# 01.net
KiCad netlist of a schematic drawn in Altium Designer
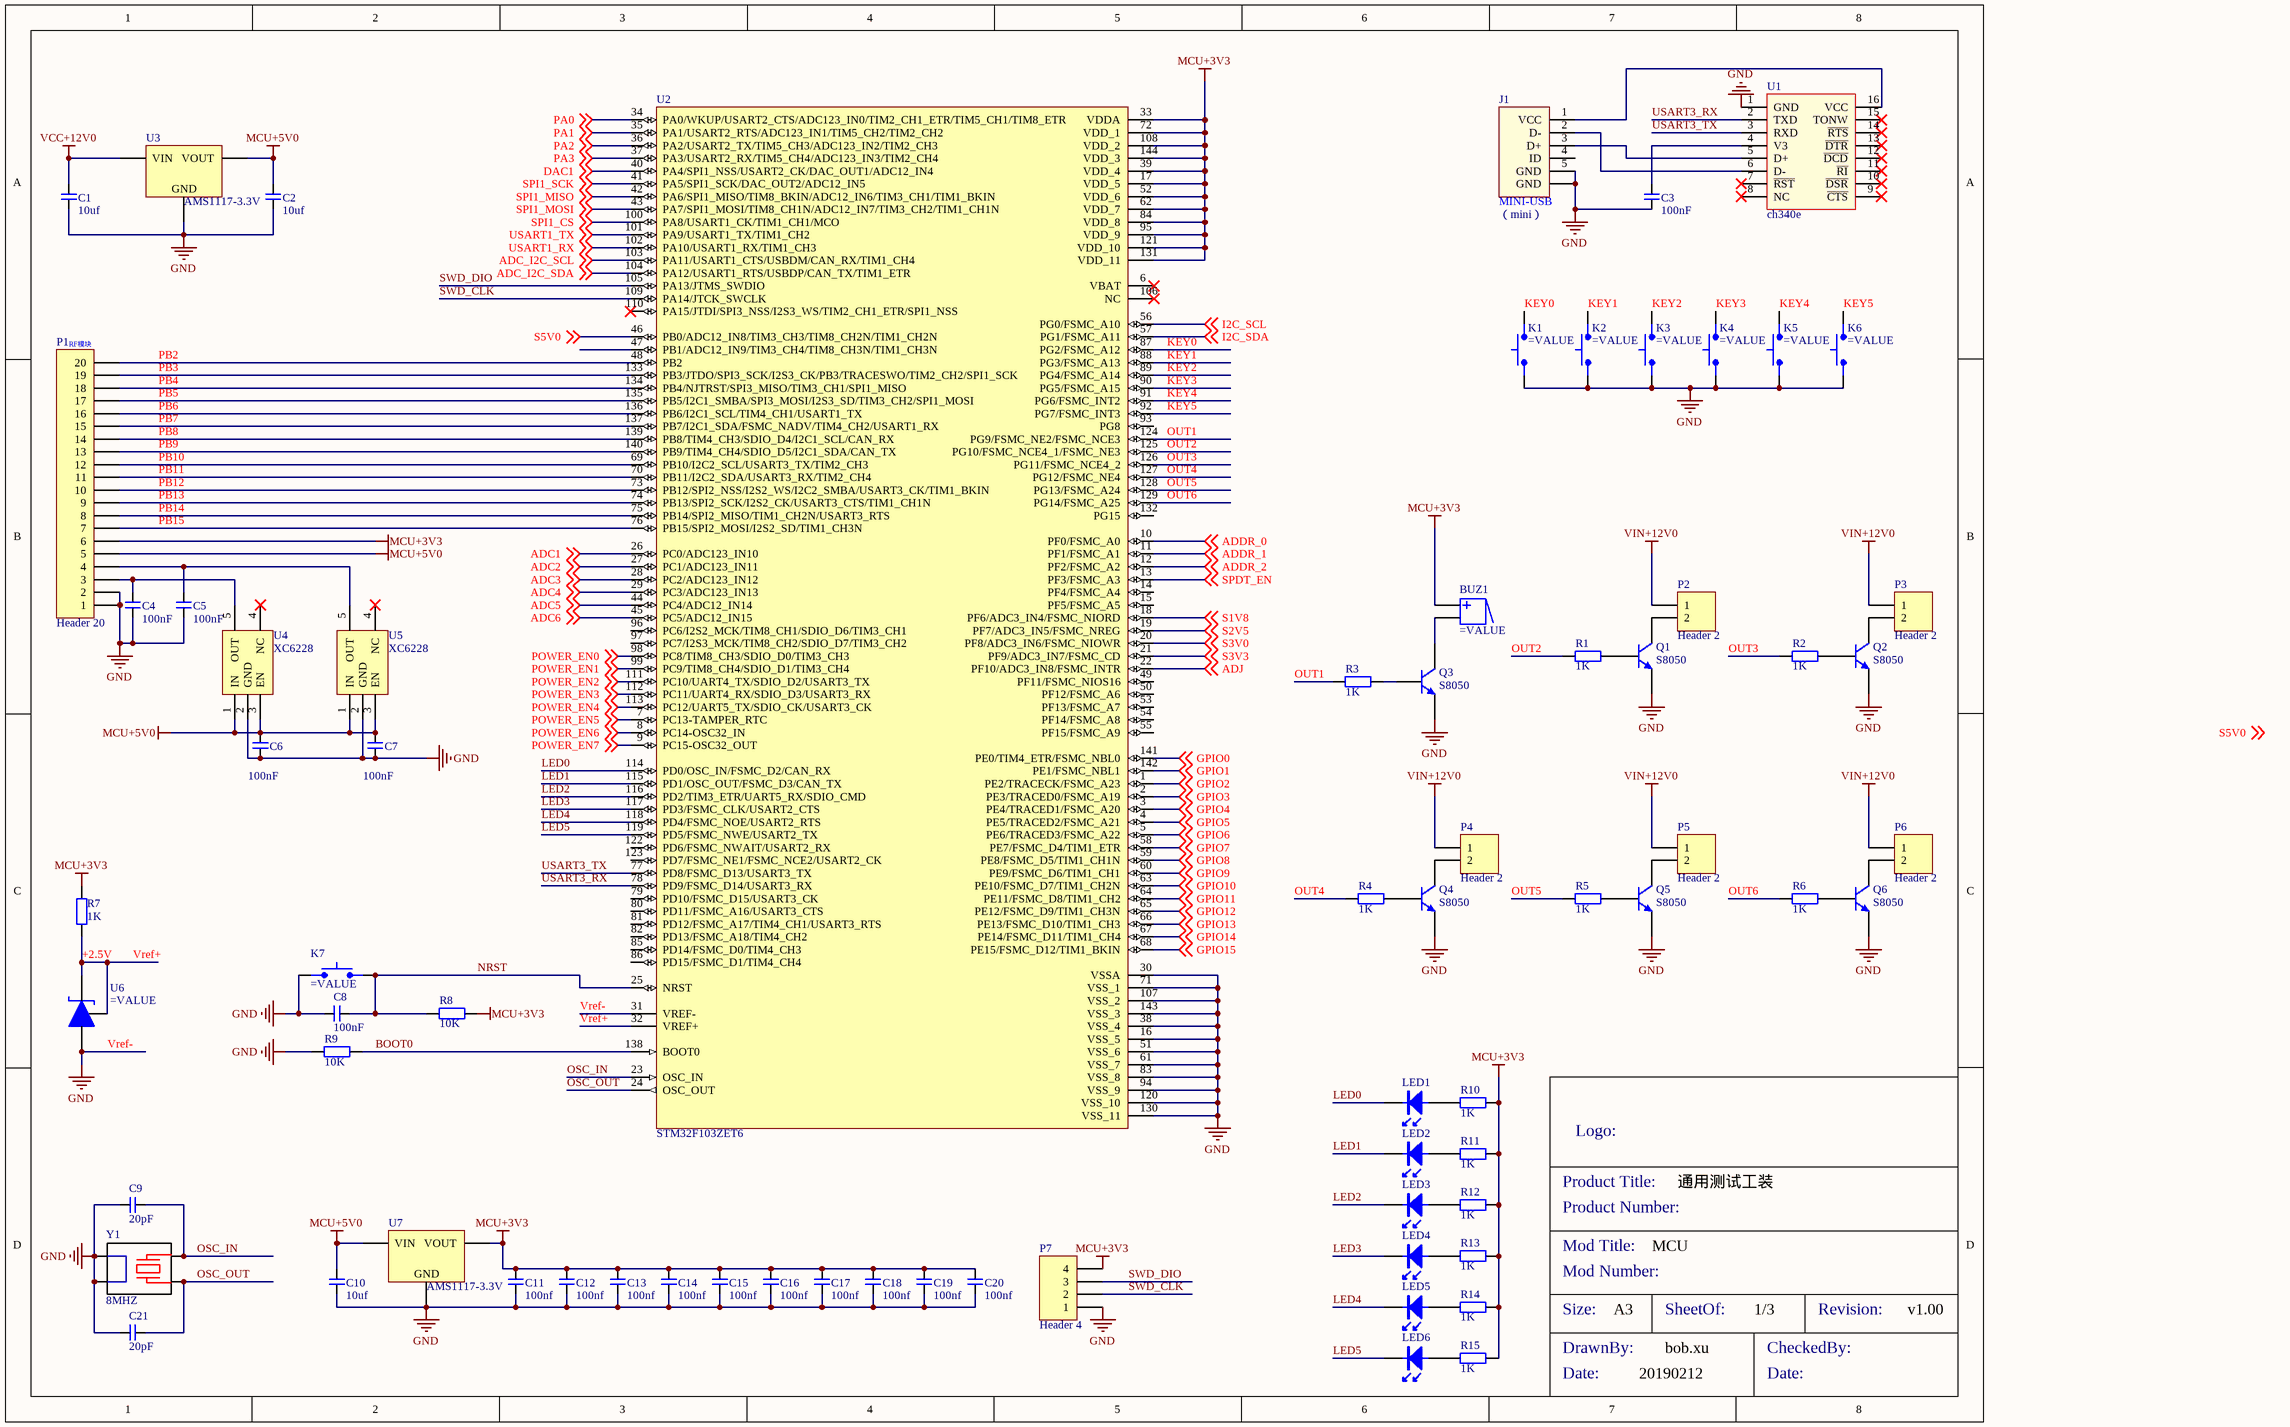
[diagram p0: 通用工装板01.SchDoc]

(export (version "E")
  (design (tool "Eeschema 10.0.6"))
  (components
    (comp (ref "BUZ1")
      (value "~")
      (footprint "DIP_BUZZER_2P_6R5_D12H9")
      (libsource (lib "瑞臻信息") (part "有源蜂鸣器"))
    )
    (comp (ref "C1")
      (value "10uf")
      (footprint "瑞臻信息:C1206")
      (description "MLCC_47uF±20%_6.3V_X5R_H1.6mm_1206")
      (fields (field (name "PART NUMBER") "1.2.04.05.0001"))
      (libsource (lib "瑞臻信息") (part "无极性电容"))
    )
    (comp (ref "C2")
      (value "10uf")
      (footprint "瑞臻信息:C1206")
      (description "MLCC_47uF±20%_6.3V_X5R_H1.6mm_1206")
      (fields (field (name "PART NUMBER") "1.2.04.05.0001"))
      (libsource (lib "瑞臻信息") (part "无极性电容"))
    )
    (comp (ref "C3")
      (value "100nF")
      (footprint "c0402")
      (description "MLCC_47uF±20%_6.3V_X5R_H1.6mm_1206")
      (fields (field (name "PART NUMBER") "1.2.04.05.0001"))
      (libsource (lib "瑞臻信息") (part "无极性电容"))
    )
    (comp (ref "C4")
      (value "100nF")
      (footprint "c0402")
      (description "MLCC_47uF±20%_6.3V_X5R_H1.6mm_1206")
      (fields (field (name "PART NUMBER") "1.2.04.05.0001"))
      (libsource (lib "瑞臻信息") (part "无极性电容"))
    )
    (comp (ref "C5")
      (value "100nF")
      (footprint "c0402")
      (description "MLCC_47uF±20%_6.3V_X5R_H1.6mm_1206")
      (fields (field (name "PART NUMBER") "1.2.04.05.0001"))
      (libsource (lib "瑞臻信息") (part "无极性电容"))
    )
    (comp (ref "C6")
      (value "100nF")
      (footprint "c0402")
      (description "MLCC_47uF±20%_6.3V_X5R_H1.6mm_1206")
      (fields (field (name "PART NUMBER") "1.2.04.05.0001"))
      (libsource (lib "瑞臻信息") (part "无极性电容"))
    )
    (comp (ref "C7")
      (value "100nF")
      (footprint "c0402")
      (description "MLCC_47uF±20%_6.3V_X5R_H1.6mm_1206")
      (fields (field (name "PART NUMBER") "1.2.04.05.0001"))
      (libsource (lib "瑞臻信息") (part "无极性电容"))
    )
    (comp (ref "C8")
      (value "100nF")
      (footprint "c0402")
      (description "MLCC_47uF±20%_6.3V_X5R_H1.6mm_1206")
      (fields (field (name "PART NUMBER") "1.2.04.05.0001"))
      (libsource (lib "瑞臻信息") (part "无极性电容"))
    )
    (comp (ref "C9")
      (value "20pF")
      (footprint "c0402")
      (description "MLCC_47uF±20%_6.3V_X5R_H1.6mm_1206")
      (fields (field (name "PART NUMBER") "1.2.04.05.0001"))
      (libsource (lib "瑞臻信息") (part "无极性电容"))
    )
    (comp (ref "C10")
      (value "10uf")
      (footprint "瑞臻信息:C1206")
      (description "MLCC_47uF±20%_6.3V_X5R_H1.6mm_1206")
      (fields (field (name "PART NUMBER") "1.2.04.05.0001"))
      (libsource (lib "瑞臻信息") (part "无极性电容"))
    )
    (comp (ref "C11")
      (value "100nf")
      (footprint "c0402")
      (description "MLCC_47uF±20%_6.3V_X5R_H1.6mm_1206")
      (fields (field (name "PART NUMBER") "1.2.04.05.0001"))
      (libsource (lib "瑞臻信息") (part "无极性电容"))
    )
    (comp (ref "C12")
      (value "100nf")
      (footprint "c0402")
      (description "MLCC_47uF±20%_6.3V_X5R_H1.6mm_1206")
      (fields (field (name "PART NUMBER") "1.2.04.05.0001"))
      (libsource (lib "瑞臻信息") (part "无极性电容"))
    )
    (comp (ref "C13")
      (value "100nf")
      (footprint "c0402")
      (description "MLCC_47uF±20%_6.3V_X5R_H1.6mm_1206")
      (fields (field (name "PART NUMBER") "1.2.04.05.0001"))
      (libsource (lib "瑞臻信息") (part "无极性电容"))
    )
    (comp (ref "C14")
      (value "100nf")
      (footprint "c0402")
      (description "MLCC_47uF±20%_6.3V_X5R_H1.6mm_1206")
      (fields (field (name "PART NUMBER") "1.2.04.05.0001"))
      (libsource (lib "瑞臻信息") (part "无极性电容"))
    )
    (comp (ref "C15")
      (value "100nf")
      (footprint "c0402")
      (description "MLCC_47uF±20%_6.3V_X5R_H1.6mm_1206")
      (fields (field (name "PART NUMBER") "1.2.04.05.0001"))
      (libsource (lib "瑞臻信息") (part "无极性电容"))
    )
    (comp (ref "C16")
      (value "100nf")
      (footprint "c0402")
      (description "MLCC_47uF±20%_6.3V_X5R_H1.6mm_1206")
      (fields (field (name "PART NUMBER") "1.2.04.05.0001"))
      (libsource (lib "瑞臻信息") (part "无极性电容"))
    )
    (comp (ref "C17")
      (value "100nf")
      (footprint "c0402")
      (description "MLCC_47uF±20%_6.3V_X5R_H1.6mm_1206")
      (fields (field (name "PART NUMBER") "1.2.04.05.0001"))
      (libsource (lib "瑞臻信息") (part "无极性电容"))
    )
    (comp (ref "C18")
      (value "100nf")
      (footprint "c0402")
      (description "MLCC_47uF±20%_6.3V_X5R_H1.6mm_1206")
      (fields (field (name "PART NUMBER") "1.2.04.05.0001"))
      (libsource (lib "瑞臻信息") (part "无极性电容"))
    )
    (comp (ref "C19")
      (value "100nf")
      (footprint "c0402")
      (description "MLCC_47uF±20%_6.3V_X5R_H1.6mm_1206")
      (fields (field (name "PART NUMBER") "1.2.04.05.0001"))
      (libsource (lib "瑞臻信息") (part "无极性电容"))
    )
    (comp (ref "C20")
      (value "100nf")
      (footprint "c0402")
      (description "MLCC_47uF±20%_6.3V_X5R_H1.6mm_1206")
      (fields (field (name "PART NUMBER") "1.2.04.05.0001"))
      (libsource (lib "瑞臻信息") (part "无极性电容"))
    )
    (comp (ref "C21")
      (value "20pF")
      (footprint "c0402")
      (description "MLCC_47uF±20%_6.3V_X5R_H1.6mm_1206")
      (fields (field (name "PART NUMBER") "1.2.04.05.0001"))
      (libsource (lib "瑞臻信息") (part "无极性电容"))
    )
    (comp (ref "J1")
      (value "（mini）")
      (footprint "DIP_MINI_USB_1")
      (libsource (lib "瑞臻信息") (part "USB座子-2（mini）"))
    )
    (comp (ref "K1") (value "~") (footprint "SMD_SWITCH_2P_3R5X6R0") (libsource (lib "瑞臻信息") (part "2脚按键-1")))
    (comp (ref "K2") (value "~") (footprint "SMD_SWITCH_2P_3R5X6R0") (libsource (lib "瑞臻信息") (part "2脚按键-1")))
    (comp (ref "K3") (value "~") (footprint "SMD_SWITCH_2P_3R5X6R0") (libsource (lib "瑞臻信息") (part "2脚按键-1")))
    (comp (ref "K4") (value "~") (footprint "SMD_SWITCH_2P_3R5X6R0") (libsource (lib "瑞臻信息") (part "2脚按键-1")))
    (comp (ref "K5") (value "~") (footprint "SMD_SWITCH_2P_3R5X6R0") (libsource (lib "瑞臻信息") (part "2脚按键-1")))
    (comp (ref "K6") (value "~") (footprint "SMD_SWITCH_2P_3R5X6R0") (libsource (lib "瑞臻信息") (part "2脚按键-1")))
    (comp (ref "K7") (value "~") (footprint "SMD_SWITCH_2P_3R5X6R0") (libsource (lib "瑞臻信息") (part "2脚按键-1")))
    (comp (ref "LED1")
      (value "~")
      (footprint "led0603+")
      (description "单LED")
      (libsource (lib "瑞臻信息") (part "单LED"))
    )
    (comp (ref "LED2")
      (value "~")
      (footprint "led0603+")
      (description "单LED")
      (libsource (lib "瑞臻信息") (part "单LED"))
    )
    (comp (ref "LED3")
      (value "~")
      (footprint "led0603+")
      (description "单LED")
      (libsource (lib "瑞臻信息") (part "单LED"))
    )
    (comp (ref "LED4")
      (value "~")
      (footprint "led0603+")
      (description "单LED")
      (libsource (lib "瑞臻信息") (part "单LED"))
    )
    (comp (ref "LED5")
      (value "~")
      (footprint "led0603+")
      (description "单LED")
      (libsource (lib "瑞臻信息") (part "单LED"))
    )
    (comp (ref "LED6")
      (value "~")
      (footprint "led0603+")
      (description "单LED")
      (libsource (lib "瑞臻信息") (part "单LED"))
    )
    (comp (ref "P1")
      (value "Header 20")
      (footprint "HDR1X20")
      (description "Header, 20-Pin")
      (libsource (lib "Miscellaneous Connectors") (part "Header 20"))
    )
    (comp (ref "P2")
      (value "Header 2")
      (footprint "HDR1X2")
      (description "Header, 2-Pin")
      (libsource (lib "Miscellaneous Connectors") (part "Header 2"))
    )
    (comp (ref "P3")
      (value "Header 2")
      (footprint "HDR1X2")
      (description "Header, 2-Pin")
      (libsource (lib "Miscellaneous Connectors") (part "Header 2"))
    )
    (comp (ref "P4")
      (value "Header 2")
      (footprint "HDR1X2")
      (description "Header, 2-Pin")
      (libsource (lib "Miscellaneous Connectors") (part "Header 2"))
    )
    (comp (ref "P5")
      (value "Header 2")
      (footprint "HDR1X2")
      (description "Header, 2-Pin")
      (libsource (lib "Miscellaneous Connectors") (part "Header 2"))
    )
    (comp (ref "P6")
      (value "Header 2")
      (footprint "HDR1X2")
      (description "Header, 2-Pin")
      (libsource (lib "Miscellaneous Connectors") (part "Header 2"))
    )
    (comp (ref "P7")
      (value "Header 4")
      (footprint "HDR1X4")
      (description "Header, 4-Pin")
      (libsource (lib "Miscellaneous Connectors") (part "Header 4"))
    )
    (comp (ref "Q1")
      (value "S8050")
      (footprint "SOT23_3P_0R95_1R6X2R9")
      (description "NPN三极管")
      (libsource (lib "瑞臻信息") (part "NPN三极管"))
    )
    (comp (ref "Q2")
      (value "S8050")
      (footprint "SOT23_3P_0R95_1R6X2R9")
      (description "NPN三极管")
      (libsource (lib "瑞臻信息") (part "NPN三极管"))
    )
    (comp (ref "Q3")
      (value "S8050")
      (footprint "SOT23_3P_0R95_1R6X2R9")
      (description "NPN三极管")
      (libsource (lib "瑞臻信息") (part "NPN三极管"))
    )
    (comp (ref "Q4")
      (value "S8050")
      (footprint "SOT23_3P_0R95_1R6X2R9")
      (description "NPN三极管")
      (libsource (lib "瑞臻信息") (part "NPN三极管"))
    )
    (comp (ref "Q5")
      (value "S8050")
      (footprint "SOT23_3P_0R95_1R6X2R9")
      (description "NPN三极管")
      (libsource (lib "瑞臻信息") (part "NPN三极管"))
    )
    (comp (ref "Q6")
      (value "S8050")
      (footprint "SOT23_3P_0R95_1R6X2R9")
      (description "NPN三极管")
      (libsource (lib "瑞臻信息") (part "NPN三极管"))
    )
    (comp (ref "R1")
      (value "1K")
      (footprint "r0402")
      (description "普通电阻")
      (libsource (lib "瑞臻信息") (part "普通电阻"))
    )
    (comp (ref "R2")
      (value "1K")
      (footprint "r0402")
      (description "普通电阻")
      (libsource (lib "瑞臻信息") (part "普通电阻"))
    )
    (comp (ref "R3")
      (value "1K")
      (footprint "r0402")
      (description "普通电阻")
      (libsource (lib "瑞臻信息") (part "普通电阻"))
    )
    (comp (ref "R4")
      (value "1K")
      (footprint "r0402")
      (description "普通电阻")
      (libsource (lib "瑞臻信息") (part "普通电阻"))
    )
    (comp (ref "R5")
      (value "1K")
      (footprint "r0402")
      (description "普通电阻")
      (libsource (lib "瑞臻信息") (part "普通电阻"))
    )
    (comp (ref "R6")
      (value "1K")
      (footprint "r0402")
      (description "普通电阻")
      (libsource (lib "瑞臻信息") (part "普通电阻"))
    )
    (comp (ref "R7")
      (value "1K")
      (footprint "R0402")
      (description "电阻-100R±5%-1/16W-0402")
      (fields (field (name "PART NUMBER") "1.2.03.01.0006"))
      (libsource (lib "") (part "普通电阻_1"))
    )
    (comp (ref "R8")
      (value "10K")
      (footprint "R0402")
      (description "电阻-100R±5%-1/16W-0402")
      (fields (field (name "PART NUMBER") "1.2.03.01.0006"))
      (libsource (lib "瑞臻信息") (part "普通电阻"))
    )
    (comp (ref "R9")
      (value "10K")
      (footprint "R0402")
      (description "电阻-100R±5%-1/16W-0402")
      (fields (field (name "PART NUMBER") "1.2.03.01.0006"))
      (libsource (lib "瑞臻信息") (part "普通电阻"))
    )
    (comp (ref "R10")
      (value "1K")
      (footprint "r0402")
      (description "普通电阻")
      (libsource (lib "瑞臻信息") (part "普通电阻"))
    )
    (comp (ref "R11")
      (value "1K")
      (footprint "r0402")
      (description "普通电阻")
      (libsource (lib "瑞臻信息") (part "普通电阻"))
    )
    (comp (ref "R12")
      (value "1K")
      (footprint "r0402")
      (description "普通电阻")
      (libsource (lib "瑞臻信息") (part "普通电阻"))
    )
    (comp (ref "R13")
      (value "1K")
      (footprint "r0402")
      (description "普通电阻")
      (libsource (lib "瑞臻信息") (part "普通电阻"))
    )
    (comp (ref "R14")
      (value "1K")
      (footprint "r0402")
      (description "普通电阻")
      (libsource (lib "瑞臻信息") (part "普通电阻"))
    )
    (comp (ref "R15")
      (value "1K")
      (footprint "r0402")
      (description "普通电阻")
      (libsource (lib "瑞臻信息") (part "普通电阻"))
    )
    (comp (ref "U1")
      (value "ch340e")
      (footprint "SOP_16P_1R27_4R0X10R0")
      (libsource (lib "瑞臻信息") (part "CH340B"))
    )
    (comp (ref "U2")
      (value "STM32F103ZET6")
      (footprint "LQFP_144P_0R5_20R0X20R0")
      (libsource (lib "瑞臻信息") (part "STM32F103ZET6"))
    )
    (comp (ref "U3")
      (value "AMS1117-3.3V")
      (footprint "SOT223_4P_2R3_3R7X6R7")
      (description "AMS1117_LDO稳压_800mA/3.3V_60dB_SOT223-3")
      (fields (field (name "PART NUMBER") "1.2.18.07.0001"))
      (libsource (lib "瑞臻信息") (part "AMS1117"))
    )
    (comp (ref "U4")
      (value "XC6228")
      (footprint "SOT23_5P_0R95_1R6X2R9")
      (libsource (lib "瑞臻信息") (part "XC6228"))
    )
    (comp (ref "U5")
      (value "XC6228")
      (footprint "SOT23_5P_0R95_1R6X2R9")
      (libsource (lib "瑞臻信息") (part "XC6228"))
    )
    (comp (ref "U6") (value "~") (footprint "SOT23_3P_0R95_1R3X2R9") (libsource (lib "瑞臻信息") (part "TL431A")))
    (comp (ref "U7")
      (value "AMS1117-3.3V")
      (footprint "SOT223_4P_2R3_3R7X6R7")
      (description "AMS1117_LDO稳压_800mA/3.3V_60dB_SOT223-3")
      (fields (field (name "PART NUMBER") "1.2.18.07.0001"))
      (libsource (lib "瑞臻信息") (part "AMS1117"))
    )
    (comp (ref "Y1")
      (value "8MHZ")
      (footprint "SMD_Crystal_4P_2R5X3R2")
      (description "四脚晶体谐振器")
      (libsource (lib "瑞臻信息") (part "四脚晶体谐振器"))
    )
  )
  (nets
    (net (code "1") (name "/+2.5V") (class "Default")
      (node (ref "R7") (pin "1") (pinfunction "1_1") (pintype "passive"))
      (node (ref "U2") (pin "32") (pinfunction "VREF+_32") (pintype "power_in"))
      (node (ref "U6") (pin "1") (pinfunction "K_1") (pintype "passive"))
      (node (ref "U6") (pin "2") (pinfunction "REF_2") (pintype "passive"))
    )
    (net (code "2") (name "/BOOT0") (class "Default")
      (node (ref "R9") (pin "2") (pinfunction "2_2") (pintype "passive"))
      (node (ref "U2") (pin "138") (pinfunction "BOOT0_138") (pintype "input"))
    )
    (net (code "3") (name "/KEY0") (class "Default")
      (node (ref "K1") (pin "2") (pinfunction "2_2") (pintype "passive"))
      (node (ref "U2") (pin "87") (pinfunction "PG2/FSMC_A12_87") (pintype "bidirectional"))
    )
    (net (code "4") (name "/KEY1") (class "Default")
      (node (ref "K2") (pin "2") (pinfunction "2_2") (pintype "passive"))
      (node (ref "U2") (pin "88") (pinfunction "PG3/FSMC_A13_88") (pintype "bidirectional"))
    )
    (net (code "5") (name "/KEY2") (class "Default")
      (node (ref "K3") (pin "2") (pinfunction "2_2") (pintype "passive"))
      (node (ref "U2") (pin "89") (pinfunction "PG4/FSMC_A14_89") (pintype "bidirectional"))
    )
    (net (code "6") (name "/KEY3") (class "Default")
      (node (ref "K4") (pin "2") (pinfunction "2_2") (pintype "passive"))
      (node (ref "U2") (pin "90") (pinfunction "PG5/FSMC_A15_90") (pintype "bidirectional"))
    )
    (net (code "7") (name "/KEY4") (class "Default")
      (node (ref "K5") (pin "2") (pinfunction "2_2") (pintype "passive"))
      (node (ref "U2") (pin "91") (pinfunction "PG6/FSMC_INT2_91") (pintype "bidirectional"))
    )
    (net (code "8") (name "/KEY5") (class "Default")
      (node (ref "K6") (pin "2") (pinfunction "2_2") (pintype "passive"))
      (node (ref "U2") (pin "92") (pinfunction "PG7/FSMC_INT3_92") (pintype "bidirectional"))
    )
    (net (code "9") (name "/LED0") (class "Default")
      (node (ref "LED1") (pin "2") (pinfunction "K_2") (pintype "passive"))
      (node (ref "U2") (pin "114") (pinfunction "PD0/OSC_IN/FSMC_D2/CAN_RX_114") (pintype "bidirectional"))
    )
    (net (code "10") (name "/LED1") (class "Default")
      (node (ref "LED2") (pin "2") (pinfunction "K_2") (pintype "passive"))
      (node (ref "U2") (pin "115") (pinfunction "PD1/OSC_OUT/FSMC_D3/CAN_TX_115") (pintype "bidirectional"))
    )
    (net (code "11") (name "/LED2") (class "Default")
      (node (ref "LED3") (pin "2") (pinfunction "K_2") (pintype "passive"))
      (node (ref "U2") (pin "116") (pinfunction "PD2/TIM3_ETR/UART5_RX/SDIO_CMD_116") (pintype "bidirectional"))
    )
    (net (code "12") (name "/LED3") (class "Default")
      (node (ref "LED4") (pin "2") (pinfunction "K_2") (pintype "passive"))
      (node (ref "U2") (pin "117") (pinfunction "PD3/FSMC_CLK/USART2_CTS_117") (pintype "bidirectional"))
    )
    (net (code "13") (name "/LED4") (class "Default")
      (node (ref "LED5") (pin "2") (pinfunction "K_2") (pintype "passive"))
      (node (ref "U2") (pin "118") (pinfunction "PD4/FSMC_NOE/USART2_RTS_118") (pintype "bidirectional"))
    )
    (net (code "14") (name "/LED5") (class "Default")
      (node (ref "LED6") (pin "2") (pinfunction "K_2") (pintype "passive"))
      (node (ref "U2") (pin "119") (pinfunction "PD5/FSMC_NWE/USART2_TX_119") (pintype "bidirectional"))
    )
    (net (code "15") (name "/NRST") (class "Default")
      (node (ref "C8") (pin "2") (pinfunction "2_2") (pintype "passive"))
      (node (ref "K7") (pin "2") (pinfunction "2_2") (pintype "passive"))
      (node (ref "R8") (pin "1") (pinfunction "1_1") (pintype "passive"))
      (node (ref "U2") (pin "25") (pinfunction "NRST_25") (pintype "bidirectional"))
    )
    (net (code "16") (name "/OSC_IN") (class "Default")
      (node (ref "C9") (pin "2") (pinfunction "2_2") (pintype "passive"))
      (node (ref "U2") (pin "23") (pinfunction "OSC_IN_23") (pintype "input"))
      (node (ref "Y1") (pin "1") (pinfunction "1_1") (pintype "passive"))
    )
    (net (code "17") (name "/OSC_OUT") (class "Default")
      (node (ref "C21") (pin "2") (pinfunction "2_2") (pintype "passive"))
      (node (ref "U2") (pin "24") (pinfunction "OSC_OUT_24") (pintype "output"))
      (node (ref "Y1") (pin "3") (pinfunction "3_3") (pintype "passive"))
    )
    (net (code "18") (name "/OUT1") (class "Default")
      (node (ref "R3") (pin "1") (pinfunction "1_1") (pintype "passive"))
      (node (ref "U2") (pin "124") (pinfunction "PG9/FSMC_NE2/FSMC_NCE3_124") (pintype "bidirectional"))
    )
    (net (code "19") (name "/OUT2") (class "Default")
      (node (ref "R1") (pin "1") (pinfunction "1_1") (pintype "passive"))
      (node (ref "U2") (pin "125") (pinfunction "PG10/FSMC_NCE4_1/FSMC_NE3_125") (pintype "bidirectional"))
    )
    (net (code "20") (name "/OUT3") (class "Default")
      (node (ref "R2") (pin "1") (pinfunction "1_1") (pintype "passive"))
      (node (ref "U2") (pin "126") (pinfunction "PG11/FSMC_NCE4_2_126") (pintype "bidirectional"))
    )
    (net (code "21") (name "/OUT4") (class "Default")
      (node (ref "R4") (pin "1") (pinfunction "1_1") (pintype "passive"))
      (node (ref "U2") (pin "127") (pinfunction "PG12/FSMC_NE4_127") (pintype "bidirectional"))
    )
    (net (code "22") (name "/OUT5") (class "Default")
      (node (ref "R5") (pin "1") (pinfunction "1_1") (pintype "passive"))
      (node (ref "U2") (pin "128") (pinfunction "PG13/FSMC_A24_128") (pintype "bidirectional"))
    )
    (net (code "23") (name "/OUT6") (class "Default")
      (node (ref "R6") (pin "1") (pinfunction "1_1") (pintype "passive"))
      (node (ref "U2") (pin "129") (pinfunction "PG14/FSMC_A25_129") (pintype "bidirectional"))
    )
    (net (code "24") (name "/PB2") (class "Default")
      (node (ref "P1") (pin "20") (pinfunction "20_20") (pintype "passive"))
      (node (ref "U2") (pin "48") (pinfunction "PB2_48") (pintype "bidirectional"))
    )
    (net (code "25") (name "/PB3") (class "Default")
      (node (ref "P1") (pin "19") (pinfunction "19_19") (pintype "passive"))
      (node (ref "U2") (pin "133") (pinfunction "PB3/JTDO/SPI3_SCK/I2S3_CK/PB3/TRACESWO/TIM2_CH2/SPI1_SCK_133") (pintype "bidirectional"))
    )
    (net (code "26") (name "/PB4") (class "Default")
      (node (ref "P1") (pin "18") (pinfunction "18_18") (pintype "passive"))
      (node (ref "U2") (pin "134") (pinfunction "PB4/NJTRST/SPI3_MISO/TIM3_CH1/SPI1_MISO_134") (pintype "bidirectional"))
    )
    (net (code "27") (name "/PB5") (class "Default")
      (node (ref "P1") (pin "17") (pinfunction "17_17") (pintype "passive"))
      (node (ref "U2") (pin "135") (pinfunction "PB5/I2C1_SMBA/SPI3_MOSI/I2S3_SD/TIM3_CH2/SPI1_MOSI_135") (pintype "bidirectional"))
    )
    (net (code "28") (name "/PB6") (class "Default")
      (node (ref "P1") (pin "16") (pinfunction "16_16") (pintype "passive"))
      (node (ref "U2") (pin "136") (pinfunction "PB6/I2C1_SCL/TIM4_CH1/USART1_TX_136") (pintype "bidirectional"))
    )
    (net (code "29") (name "/PB7") (class "Default")
      (node (ref "P1") (pin "15") (pinfunction "15_15") (pintype "passive"))
      (node (ref "U2") (pin "137") (pinfunction "PB7/I2C1_SDA/FSMC_NADV/TIM4_CH2/USART1_RX_137") (pintype "bidirectional"))
    )
    (net (code "30") (name "/PB8") (class "Default")
      (node (ref "P1") (pin "14") (pinfunction "14_14") (pintype "passive"))
      (node (ref "U2") (pin "139") (pinfunction "PB8/TIM4_CH3/SDIO_D4/I2C1_SCL/CAN_RX_139") (pintype "bidirectional"))
    )
    (net (code "31") (name "/PB9") (class "Default")
      (node (ref "P1") (pin "13") (pinfunction "13_13") (pintype "passive"))
      (node (ref "U2") (pin "140") (pinfunction "PB9/TIM4_CH4/SDIO_D5/I2C1_SDA/CAN_TX_140") (pintype "bidirectional"))
    )
    (net (code "32") (name "/PB10") (class "Default")
      (node (ref "P1") (pin "12") (pinfunction "12_12") (pintype "passive"))
      (node (ref "U2") (pin "69") (pinfunction "PB10/I2C2_SCL/USART3_TX/TIM2_CH3_69") (pintype "bidirectional"))
    )
    (net (code "33") (name "/PB11") (class "Default")
      (node (ref "P1") (pin "11") (pinfunction "11_11") (pintype "passive"))
      (node (ref "U2") (pin "70") (pinfunction "PB11/I2C2_SDA/USART3_RX/TIM2_CH4_70") (pintype "bidirectional"))
    )
    (net (code "34") (name "/PB12") (class "Default")
      (node (ref "P1") (pin "10") (pinfunction "10_10") (pintype "passive"))
      (node (ref "U2") (pin "73") (pinfunction "PB12/SPI2_NSS/I2S2_WS/I2C2_SMBA/USART3_CK/TIM1_BKIN_73") (pintype "bidirectional"))
    )
    (net (code "35") (name "/PB13") (class "Default")
      (node (ref "P1") (pin "9") (pinfunction "9_9") (pintype "passive"))
      (node (ref "U2") (pin "74") (pinfunction "PB13/SPI2_SCK/I2S2_CK/USART3_CTS/TIM1_CH1N_74") (pintype "bidirectional"))
    )
    (net (code "36") (name "/PB14") (class "Default")
      (node (ref "P1") (pin "8") (pinfunction "8_8") (pintype "passive"))
      (node (ref "U2") (pin "75") (pinfunction "PB14/SPI2_MISO/TIM1_CH2N/USART3_RTS_75") (pintype "bidirectional"))
    )
    (net (code "37") (name "/PB15") (class "Default")
      (node (ref "P1") (pin "7") (pinfunction "7_7") (pintype "passive"))
      (node (ref "U2") (pin "76") (pinfunction "PB15/SPI2_MOSI/I2S2_SD/TIM1_CH3N_76") (pintype "bidirectional"))
    )
    (net (code "38") (name "/SWD_CLK") (class "Default")
      (node (ref "P7") (pin "2") (pinfunction "2_2") (pintype "passive"))
      (node (ref "U2") (pin "109") (pinfunction "PA14/JTCK_SWCLK_109") (pintype "bidirectional"))
    )
    (net (code "39") (name "/SWD_DIO") (class "Default")
      (node (ref "P7") (pin "3") (pinfunction "3_3") (pintype "passive"))
      (node (ref "U2") (pin "105") (pinfunction "PA13/JTMS_SWDIO_105") (pintype "bidirectional"))
    )
    (net (code "40") (name "/USART3_RX") (class "Default")
      (node (ref "U1") (pin "2") (pinfunction "TXD_2") (pintype "passive"))
      (node (ref "U2") (pin "78") (pinfunction "PD9/FSMC_D14/USART3_RX_78") (pintype "bidirectional"))
    )
    (net (code "41") (name "/USART3_TX") (class "Default")
      (node (ref "U1") (pin "3") (pinfunction "RXD_3") (pintype "passive"))
      (node (ref "U2") (pin "77") (pinfunction "PD8/FSMC_D13/USART3_TX_77") (pintype "bidirectional"))
    )
    (net (code "42") (name "ADC1") (class "Default")
      (node (ref "U2") (pin "26") (pinfunction "PC0/ADC123_IN10_26") (pintype "bidirectional"))
    )
    (net (code "43") (name "ADC2") (class "Default")
      (node (ref "U2") (pin "27") (pinfunction "PC1/ADC123_IN11_27") (pintype "bidirectional"))
    )
    (net (code "44") (name "ADC3") (class "Default")
      (node (ref "U2") (pin "28") (pinfunction "PC2/ADC123_IN12_28") (pintype "bidirectional"))
    )
    (net (code "45") (name "ADC4") (class "Default")
      (node (ref "U2") (pin "29") (pinfunction "PC3/ADC123_IN13_29") (pintype "bidirectional"))
    )
    (net (code "46") (name "ADC5") (class "Default")
      (node (ref "U2") (pin "44") (pinfunction "PC4/ADC12_IN14_44") (pintype "bidirectional"))
    )
    (net (code "47") (name "ADC6") (class "Default")
      (node (ref "U2") (pin "45") (pinfunction "PC5/ADC12_IN15_45") (pintype "bidirectional"))
    )
    (net (code "48") (name "ADC_I2C_SCL") (class "Default")
      (node (ref "U2") (pin "103") (pinfunction "PA11/USART1_CTS/USBDM/CAN_RX/TIM1_CH4_103") (pintype "bidirectional"))
    )
    (net (code "49") (name "ADC_I2C_SDA") (class "Default")
      (node (ref "U2") (pin "104") (pinfunction "PA12/USART1_RTS/USBDP/CAN_TX/TIM1_ETR_104") (pintype "bidirectional"))
    )
    (net (code "50") (name "ADDR_0") (class "Default")
      (node (ref "U2") (pin "10") (pinfunction "PF0/FSMC_A0_10") (pintype "bidirectional"))
    )
    (net (code "51") (name "ADDR_1") (class "Default")
      (node (ref "U2") (pin "11") (pinfunction "PF1/FSMC_A1_11") (pintype "bidirectional"))
    )
    (net (code "52") (name "ADDR_2") (class "Default")
      (node (ref "U2") (pin "12") (pinfunction "PF2/FSMC_A2_12") (pintype "bidirectional"))
    )
    (net (code "53") (name "ADJ") (class "Default")
      (node (ref "U2") (pin "22") (pinfunction "PF10/ADC3_IN8/FSMC_INTR_22") (pintype "bidirectional"))
    )
    (net (code "54") (name "DAC1") (class "Default")
      (node (ref "U2") (pin "40") (pinfunction "PA4/SPI1_NSS/USART2_CK/DAC_OUT1/ADC12_IN4_40") (pintype "bidirectional"))
    )
    (net (code "55") (name "GND") (class "Default")
      (node (ref "C1") (pin "1") (pinfunction "1_1") (pintype "passive"))
      (node (ref "C10") (pin "1") (pinfunction "1_1") (pintype "passive"))
      (node (ref "C11") (pin "1") (pinfunction "1_1") (pintype "passive"))
      (node (ref "C12") (pin "1") (pinfunction "1_1") (pintype "passive"))
      (node (ref "C13") (pin "1") (pinfunction "1_1") (pintype "passive"))
      (node (ref "C14") (pin "1") (pinfunction "1_1") (pintype "passive"))
      (node (ref "C15") (pin "1") (pinfunction "1_1") (pintype "passive"))
      (node (ref "C16") (pin "1") (pinfunction "1_1") (pintype "passive"))
      (node (ref "C17") (pin "1") (pinfunction "1_1") (pintype "passive"))
      (node (ref "C18") (pin "1") (pinfunction "1_1") (pintype "passive"))
      (node (ref "C19") (pin "1") (pinfunction "1_1") (pintype "passive"))
      (node (ref "C2") (pin "1") (pinfunction "1_1") (pintype "passive"))
      (node (ref "C20") (pin "1") (pinfunction "1_1") (pintype "passive"))
      (node (ref "C21") (pin "1") (pinfunction "1_1") (pintype "passive"))
      (node (ref "C3") (pin "1") (pinfunction "1_1") (pintype "passive"))
      (node (ref "C4") (pin "2") (pinfunction "2_2") (pintype "passive"))
      (node (ref "C5") (pin "2") (pinfunction "2_2") (pintype "passive"))
      (node (ref "C6") (pin "1") (pinfunction "1_1") (pintype "passive"))
      (node (ref "C7") (pin "1") (pinfunction "1_1") (pintype "passive"))
      (node (ref "C8") (pin "1") (pinfunction "1_1") (pintype "passive"))
      (node (ref "C9") (pin "1") (pinfunction "1_1") (pintype "passive"))
      (node (ref "J1") (pin "5") (pinfunction "GND_5") (pintype "passive"))
      (node (ref "J1") (pin "A") (pinfunction "GND_A") (pintype "passive"))
      (node (ref "K1") (pin "1") (pinfunction "1_1") (pintype "passive"))
      (node (ref "K2") (pin "1") (pinfunction "1_1") (pintype "passive"))
      (node (ref "K3") (pin "1") (pinfunction "1_1") (pintype "passive"))
      (node (ref "K4") (pin "1") (pinfunction "1_1") (pintype "passive"))
      (node (ref "K5") (pin "1") (pinfunction "1_1") (pintype "passive"))
      (node (ref "K6") (pin "1") (pinfunction "1_1") (pintype "passive"))
      (node (ref "K7") (pin "1") (pinfunction "1_1") (pintype "passive"))
      (node (ref "P1") (pin "1") (pinfunction "1_1") (pintype "passive"))
      (node (ref "P1") (pin "2") (pinfunction "2_2") (pintype "passive"))
      (node (ref "P7") (pin "1") (pinfunction "1_1") (pintype "passive"))
      (node (ref "Q1") (pin "2") (pinfunction "E_2") (pintype "passive"))
      (node (ref "Q2") (pin "2") (pinfunction "E_2") (pintype "passive"))
      (node (ref "Q3") (pin "2") (pinfunction "E_2") (pintype "passive"))
      (node (ref "Q4") (pin "2") (pinfunction "E_2") (pintype "passive"))
      (node (ref "Q5") (pin "2") (pinfunction "E_2") (pintype "passive"))
      (node (ref "Q6") (pin "2") (pinfunction "E_2") (pintype "passive"))
      (node (ref "R9") (pin "1") (pinfunction "1_1") (pintype "passive"))
      (node (ref "U1") (pin "1") (pinfunction "GND_1") (pintype "passive"))
      (node (ref "U2") (pin "107") (pinfunction "VSS_2_107") (pintype "power_in"))
      (node (ref "U2") (pin "120") (pinfunction "VSS_10_120") (pintype "power_in"))
      (node (ref "U2") (pin "130") (pinfunction "VSS_11_130") (pintype "power_in"))
      (node (ref "U2") (pin "143") (pinfunction "VSS_3_143") (pintype "power_in"))
      (node (ref "U2") (pin "16") (pinfunction "VSS_5_16") (pintype "power_in"))
      (node (ref "U2") (pin "30") (pinfunction "VSSA_30") (pintype "power_in"))
      (node (ref "U2") (pin "31") (pinfunction "VREF-_31") (pintype "power_in"))
      (node (ref "U2") (pin "38") (pinfunction "VSS_4_38") (pintype "power_in"))
      (node (ref "U2") (pin "51") (pinfunction "VSS_6_51") (pintype "power_in"))
      (node (ref "U2") (pin "61") (pinfunction "VSS_7_61") (pintype "power_in"))
      (node (ref "U2") (pin "71") (pinfunction "VSS_1_71") (pintype "power_in"))
      (node (ref "U2") (pin "83") (pinfunction "VSS_8_83") (pintype "power_in"))
      (node (ref "U2") (pin "94") (pinfunction "VSS_9_94") (pintype "power_in"))
      (node (ref "U3") (pin "1") (pinfunction "GND_1") (pintype "passive"))
      (node (ref "U4") (pin "2") (pinfunction "GND_2") (pintype "passive"))
      (node (ref "U5") (pin "2") (pinfunction "GND_2") (pintype "passive"))
      (node (ref "U6") (pin "3") (pinfunction "A_3") (pintype "passive"))
      (node (ref "U7") (pin "1") (pinfunction "GND_1") (pintype "passive"))
      (node (ref "Y1") (pin "2") (pinfunction "2_2") (pintype "passive"))
      (node (ref "Y1") (pin "4") (pinfunction "4_4") (pintype "passive"))
    )
    (net (code "56") (name "GPIO0") (class "Default")
      (node (ref "U2") (pin "141") (pinfunction "PE0/TIM4_ETR/FSMC_NBL0_141") (pintype "bidirectional"))
    )
    (net (code "57") (name "GPIO1") (class "Default")
      (node (ref "U2") (pin "142") (pinfunction "PE1/FSMC_NBL1_142") (pintype "bidirectional"))
    )
    (net (code "58") (name "GPIO2") (class "Default")
      (node (ref "U2") (pin "1") (pinfunction "PE2/TRACECK/FSMC_A23_1") (pintype "bidirectional"))
    )
    (net (code "59") (name "GPIO3") (class "Default")
      (node (ref "U2") (pin "2") (pinfunction "PE3/TRACED0/FSMC_A19_2") (pintype "bidirectional"))
    )
    (net (code "60") (name "GPIO4") (class "Default")
      (node (ref "U2") (pin "3") (pinfunction "PE4/TRACED1/FSMC_A20_3") (pintype "bidirectional"))
    )
    (net (code "61") (name "GPIO5") (class "Default")
      (node (ref "U2") (pin "4") (pinfunction "PE5/TRACED2/FSMC_A21_4") (pintype "bidirectional"))
    )
    (net (code "62") (name "GPIO6") (class "Default")
      (node (ref "U2") (pin "5") (pinfunction "PE6/TRACED3/FSMC_A22_5") (pintype "bidirectional"))
    )
    (net (code "63") (name "GPIO7") (class "Default")
      (node (ref "U2") (pin "58") (pinfunction "PE7/FSMC_D4/TIM1_ETR_58") (pintype "bidirectional"))
    )
    (net (code "64") (name "GPIO8") (class "Default")
      (node (ref "U2") (pin "59") (pinfunction "PE8/FSMC_D5/TIM1_CH1N_59") (pintype "bidirectional"))
    )
    (net (code "65") (name "GPIO9") (class "Default")
      (node (ref "U2") (pin "60") (pinfunction "PE9/FSMC_D6/TIM1_CH1_60") (pintype "bidirectional"))
    )
    (net (code "66") (name "GPIO10") (class "Default")
      (node (ref "U2") (pin "63") (pinfunction "PE10/FSMC_D7/TIM1_CH2N_63") (pintype "bidirectional"))
    )
    (net (code "67") (name "GPIO11") (class "Default")
      (node (ref "U2") (pin "64") (pinfunction "PE11/FSMC_D8/TIM1_CH2_64") (pintype "bidirectional"))
    )
    (net (code "68") (name "GPIO12") (class "Default")
      (node (ref "U2") (pin "65") (pinfunction "PE12/FSMC_D9/TIM1_CH3N_65") (pintype "bidirectional"))
    )
    (net (code "69") (name "GPIO13") (class "Default")
      (node (ref "U2") (pin "66") (pinfunction "PE13/FSMC_D10/TIM1_CH3_66") (pintype "bidirectional"))
    )
    (net (code "70") (name "GPIO14") (class "Default")
      (node (ref "U2") (pin "67") (pinfunction "PE14/FSMC_D11/TIM1_CH4_67") (pintype "bidirectional"))
    )
    (net (code "71") (name "GPIO15") (class "Default")
      (node (ref "U2") (pin "68") (pinfunction "PE15/FSMC_D12/TIM1_BKIN_68") (pintype "bidirectional"))
    )
    (net (code "72") (name "I2C_SCL") (class "Default")
      (node (ref "U2") (pin "56") (pinfunction "PG0/FSMC_A10_56") (pintype "bidirectional"))
    )
    (net (code "73") (name "I2C_SDA") (class "Default")
      (node (ref "U2") (pin "57") (pinfunction "PG1/FSMC_A11_57") (pintype "bidirectional"))
    )
    (net (code "74") (name "MCU+3V3") (class "Default")
      (node (ref "BUZ1") (pin "1") (pinfunction "1_1") (pintype "passive"))
      (node (ref "C11") (pin "2") (pinfunction "2_2") (pintype "passive"))
      (node (ref "C12") (pin "2") (pinfunction "2_2") (pintype "passive"))
      (node (ref "C13") (pin "2") (pinfunction "2_2") (pintype "passive"))
      (node (ref "C14") (pin "2") (pinfunction "2_2") (pintype "passive"))
      (node (ref "C15") (pin "2") (pinfunction "2_2") (pintype "passive"))
      (node (ref "C16") (pin "2") (pinfunction "2_2") (pintype "passive"))
      (node (ref "C17") (pin "2") (pinfunction "2_2") (pintype "passive"))
      (node (ref "C18") (pin "2") (pinfunction "2_2") (pintype "passive"))
      (node (ref "C19") (pin "2") (pinfunction "2_2") (pintype "passive"))
      (node (ref "C20") (pin "2") (pinfunction "2_2") (pintype "passive"))
      (node (ref "P1") (pin "6") (pinfunction "6_6") (pintype "passive"))
      (node (ref "P7") (pin "4") (pinfunction "4_4") (pintype "passive"))
      (node (ref "R10") (pin "2") (pinfunction "2_2") (pintype "passive"))
      (node (ref "R11") (pin "2") (pinfunction "2_2") (pintype "passive"))
      (node (ref "R12") (pin "2") (pinfunction "2_2") (pintype "passive"))
      (node (ref "R13") (pin "2") (pinfunction "2_2") (pintype "passive"))
      (node (ref "R14") (pin "2") (pinfunction "2_2") (pintype "passive"))
      (node (ref "R15") (pin "2") (pinfunction "2_2") (pintype "passive"))
      (node (ref "R7") (pin "2") (pinfunction "2_2") (pintype "passive"))
      (node (ref "R8") (pin "2") (pinfunction "2_2") (pintype "passive"))
      (node (ref "U2") (pin "108") (pinfunction "VDD_2_108") (pintype "power_in"))
      (node (ref "U2") (pin "121") (pinfunction "VDD_10_121") (pintype "power_in"))
      (node (ref "U2") (pin "131") (pinfunction "VDD_11_131") (pintype "power_in"))
      (node (ref "U2") (pin "144") (pinfunction "VDD_3_144") (pintype "power_in"))
      (node (ref "U2") (pin "17") (pinfunction "VDD_5_17") (pintype "power_in"))
      (node (ref "U2") (pin "33") (pinfunction "VDDA_33") (pintype "power_in"))
      (node (ref "U2") (pin "39") (pinfunction "VDD_4_39") (pintype "power_in"))
      (node (ref "U2") (pin "52") (pinfunction "VDD_6_52") (pintype "power_in"))
      (node (ref "U2") (pin "62") (pinfunction "VDD_7_62") (pintype "power_in"))
      (node (ref "U2") (pin "72") (pinfunction "VDD_1_72") (pintype "power_in"))
      (node (ref "U2") (pin "84") (pinfunction "VDD_8_84") (pintype "power_in"))
      (node (ref "U2") (pin "95") (pinfunction "VDD_9_95") (pintype "power_in"))
      (node (ref "U7") (pin "2") (pinfunction "VOUT_2") (pintype "passive"))
    )
    (net (code "75") (name "MCU+5V0") (class "Default")
      (node (ref "C10") (pin "2") (pinfunction "2_2") (pintype "passive"))
      (node (ref "C2") (pin "2") (pinfunction "2_2") (pintype "passive"))
      (node (ref "C6") (pin "2") (pinfunction "2_2") (pintype "passive"))
      (node (ref "C7") (pin "2") (pinfunction "2_2") (pintype "passive"))
      (node (ref "P1") (pin "5") (pinfunction "5_5") (pintype "passive"))
      (node (ref "U3") (pin "2") (pinfunction "VOUT_2") (pintype "passive"))
      (node (ref "U4") (pin "1") (pinfunction "IN_1") (pintype "passive"))
      (node (ref "U4") (pin "3") (pinfunction "EN_3") (pintype "passive"))
      (node (ref "U5") (pin "1") (pinfunction "IN_1") (pintype "passive"))
      (node (ref "U5") (pin "3") (pinfunction "EN_3") (pintype "passive"))
      (node (ref "U7") (pin "3") (pinfunction "VIN_3") (pintype "passive"))
    )
    (net (code "76") (name "Net-(J1-D+)") (class "Default")
      (node (ref "J1") (pin "3") (pinfunction "D+_3") (pintype "passive"))
      (node (ref "U1") (pin "5") (pinfunction "D+_5") (pintype "passive"))
    )
    (net (code "77") (name "Net-(J1-D-)") (class "Default")
      (node (ref "J1") (pin "2") (pinfunction "D-_2") (pintype "passive"))
      (node (ref "U1") (pin "6") (pinfunction "D-_6") (pintype "passive"))
    )
    (net (code "78") (name "Net-(J1-VCC)") (class "Default")
      (node (ref "J1") (pin "1") (pinfunction "VCC_1") (pintype "passive"))
      (node (ref "U1") (pin "16") (pinfunction "VCC_16") (pintype "passive"))
    )
    (net (code "79") (name "Net-(LED1-A)") (class "Default")
      (node (ref "LED1") (pin "1") (pinfunction "A_1") (pintype "passive"))
      (node (ref "R10") (pin "1") (pinfunction "1_1") (pintype "passive"))
    )
    (net (code "80") (name "Net-(LED2-A)") (class "Default")
      (node (ref "LED2") (pin "1") (pinfunction "A_1") (pintype "passive"))
      (node (ref "R11") (pin "1") (pinfunction "1_1") (pintype "passive"))
    )
    (net (code "81") (name "Net-(LED3-A)") (class "Default")
      (node (ref "LED3") (pin "1") (pinfunction "A_1") (pintype "passive"))
      (node (ref "R12") (pin "1") (pinfunction "1_1") (pintype "passive"))
    )
    (net (code "82") (name "Net-(LED4-A)") (class "Default")
      (node (ref "LED4") (pin "1") (pinfunction "A_1") (pintype "passive"))
      (node (ref "R13") (pin "1") (pinfunction "1_1") (pintype "passive"))
    )
    (net (code "83") (name "Net-(LED5-A)") (class "Default")
      (node (ref "LED5") (pin "1") (pinfunction "A_1") (pintype "passive"))
      (node (ref "R14") (pin "1") (pinfunction "1_1") (pintype "passive"))
    )
    (net (code "84") (name "Net-(LED6-A)") (class "Default")
      (node (ref "LED6") (pin "1") (pinfunction "A_1") (pintype "passive"))
      (node (ref "R15") (pin "1") (pinfunction "1_1") (pintype "passive"))
    )
    (net (code "85") (name "Net-(Q1-B)") (class "Default")
      (node (ref "Q1") (pin "1") (pinfunction "B_1") (pintype "passive"))
      (node (ref "R1") (pin "2") (pinfunction "2_2") (pintype "passive"))
    )
    (net (code "86") (name "Net-(Q1-C)") (class "Default")
      (node (ref "P2") (pin "2") (pinfunction "2_2") (pintype "passive"))
      (node (ref "Q1") (pin "3") (pinfunction "C_3") (pintype "passive"))
    )
    (net (code "87") (name "Net-(Q2-B)") (class "Default")
      (node (ref "Q2") (pin "1") (pinfunction "B_1") (pintype "passive"))
      (node (ref "R2") (pin "2") (pinfunction "2_2") (pintype "passive"))
    )
    (net (code "88") (name "Net-(Q2-C)") (class "Default")
      (node (ref "P3") (pin "2") (pinfunction "2_2") (pintype "passive"))
      (node (ref "Q2") (pin "3") (pinfunction "C_3") (pintype "passive"))
    )
    (net (code "89") (name "Net-(Q3-B)") (class "Default")
      (node (ref "Q3") (pin "1") (pinfunction "B_1") (pintype "passive"))
      (node (ref "R3") (pin "2") (pinfunction "2_2") (pintype "passive"))
    )
    (net (code "90") (name "Net-(Q3-C)") (class "Default")
      (node (ref "BUZ1") (pin "2") (pinfunction "2_2") (pintype "passive"))
      (node (ref "Q3") (pin "3") (pinfunction "C_3") (pintype "passive"))
    )
    (net (code "91") (name "Net-(Q4-B)") (class "Default")
      (node (ref "Q4") (pin "1") (pinfunction "B_1") (pintype "passive"))
      (node (ref "R4") (pin "2") (pinfunction "2_2") (pintype "passive"))
    )
    (net (code "92") (name "Net-(Q4-C)") (class "Default")
      (node (ref "P4") (pin "2") (pinfunction "2_2") (pintype "passive"))
      (node (ref "Q4") (pin "3") (pinfunction "C_3") (pintype "passive"))
    )
    (net (code "93") (name "Net-(Q5-B)") (class "Default")
      (node (ref "Q5") (pin "1") (pinfunction "B_1") (pintype "passive"))
      (node (ref "R5") (pin "2") (pinfunction "2_2") (pintype "passive"))
    )
    (net (code "94") (name "Net-(Q5-C)") (class "Default")
      (node (ref "P5") (pin "2") (pinfunction "2_2") (pintype "passive"))
      (node (ref "Q5") (pin "3") (pinfunction "C_3") (pintype "passive"))
    )
    (net (code "95") (name "Net-(Q6-B)") (class "Default")
      (node (ref "Q6") (pin "1") (pinfunction "B_1") (pintype "passive"))
      (node (ref "R6") (pin "2") (pinfunction "2_2") (pintype "passive"))
    )
    (net (code "96") (name "Net-(Q6-C)") (class "Default")
      (node (ref "P6") (pin "2") (pinfunction "2_2") (pintype "passive"))
      (node (ref "Q6") (pin "3") (pinfunction "C_3") (pintype "passive"))
    )
    (net (code "97") (name "Net-(U1-V3)") (class "Default")
      (node (ref "C3") (pin "2") (pinfunction "2_2") (pintype "passive"))
      (node (ref "U1") (pin "4") (pinfunction "V3_4") (pintype "passive"))
    )
    (net (code "98") (name "Net-(U4-OUT)") (class "Default")
      (node (ref "C4") (pin "1") (pinfunction "1_1") (pintype "passive"))
      (node (ref "P1") (pin "3") (pinfunction "3_3") (pintype "passive"))
      (node (ref "U4") (pin "5") (pinfunction "OUT_5") (pintype "passive"))
    )
    (net (code "99") (name "Net-(U5-OUT)") (class "Default")
      (node (ref "C5") (pin "1") (pinfunction "1_1") (pintype "passive"))
      (node (ref "P1") (pin "4") (pinfunction "4_4") (pintype "passive"))
      (node (ref "U5") (pin "5") (pinfunction "OUT_5") (pintype "passive"))
    )
    (net (code "100") (name "PA0") (class "Default")
      (node (ref "U2") (pin "34") (pinfunction "PA0/WKUP/USART2_CTS/ADC123_IN0/TIM2_CH1_ETR/TIM5_CH1/TIM8_ETR_34") (pintype "bidirectional"))
    )
    (net (code "101") (name "PA1") (class "Default")
      (node (ref "U2") (pin "35") (pinfunction "PA1/USART2_RTS/ADC123_IN1/TIM5_CH2/TIM2_CH2_35") (pintype "bidirectional"))
    )
    (net (code "102") (name "PA2") (class "Default")
      (node (ref "U2") (pin "36") (pinfunction "PA2/USART2_TX/TIM5_CH3/ADC123_IN2/TIM2_CH3_36") (pintype "bidirectional"))
    )
    (net (code "103") (name "PA3") (class "Default")
      (node (ref "U2") (pin "37") (pinfunction "PA3/USART2_RX/TIM5_CH4/ADC123_IN3/TIM2_CH4_37") (pintype "bidirectional"))
    )
    (net (code "104") (name "POWER_EN0") (class "Default")
      (node (ref "U2") (pin "98") (pinfunction "PC8/TIM8_CH3/SDIO_D0/TIM3_CH3_98") (pintype "bidirectional"))
    )
    (net (code "105") (name "POWER_EN1") (class "Default")
      (node (ref "U2") (pin "99") (pinfunction "PC9/TIM8_CH4/SDIO_D1/TIM3_CH4_99") (pintype "bidirectional"))
    )
    (net (code "106") (name "POWER_EN2") (class "Default")
      (node (ref "U2") (pin "111") (pinfunction "PC10/UART4_TX/SDIO_D2/USART3_TX_111") (pintype "bidirectional"))
    )
    (net (code "107") (name "POWER_EN3") (class "Default")
      (node (ref "U2") (pin "112") (pinfunction "PC11/UART4_RX/SDIO_D3/USART3_RX_112") (pintype "bidirectional"))
    )
    (net (code "108") (name "POWER_EN4") (class "Default")
      (node (ref "U2") (pin "113") (pinfunction "PC12/UART5_TX/SDIO_CK/USART3_CK_113") (pintype "bidirectional"))
    )
    (net (code "109") (name "POWER_EN5") (class "Default")
      (node (ref "U2") (pin "7") (pinfunction "PC13-TAMPER_RTC_7") (pintype "bidirectional"))
    )
    (net (code "110") (name "POWER_EN6") (class "Default")
      (node (ref "U2") (pin "8") (pinfunction "PC14-OSC32_IN_8") (pintype "bidirectional"))
    )
    (net (code "111") (name "POWER_EN7") (class "Default")
      (node (ref "U2") (pin "9") (pinfunction "PC15-OSC32_OUT_9") (pintype "bidirectional"))
    )
    (net (code "112") (name "S1V8") (class "Default")
      (node (ref "U2") (pin "18") (pinfunction "PF6/ADC3_IN4/FSMC_NIORD_18") (pintype "bidirectional"))
    )
    (net (code "113") (name "S2V5") (class "Default")
      (node (ref "U2") (pin "19") (pinfunction "PF7/ADC3_IN5/FSMC_NREG_19") (pintype "bidirectional"))
    )
    (net (code "114") (name "S3V0") (class "Default")
      (node (ref "U2") (pin "20") (pinfunction "PF8/ADC3_IN6/FSMC_NIOWR_20") (pintype "bidirectional"))
    )
    (net (code "115") (name "S3V3") (class "Default")
      (node (ref "U2") (pin "21") (pinfunction "PF9/ADC3_IN7/FSMC_CD_21") (pintype "bidirectional"))
    )
    (net (code "116") (name "S5V0") (class "Default")
      (node (ref "U2") (pin "46") (pinfunction "PB0/ADC12_IN8/TIM3_CH3/TIM8_CH2N/TIM1_CH2N_46") (pintype "bidirectional"))
    )
    (net (code "117") (name "SPDT_EN") (class "Default")
      (node (ref "U2") (pin "13") (pinfunction "PF3/FSMC_A3_13") (pintype "bidirectional"))
    )
    (net (code "118") (name "SPI1_CS") (class "Default")
      (node (ref "U2") (pin "100") (pinfunction "PA8/USART1_CK/TIM1_CH1/MCO_100") (pintype "bidirectional"))
    )
    (net (code "119") (name "SPI1_MISO") (class "Default")
      (node (ref "U2") (pin "42") (pinfunction "PA6/SPI1_MISO/TIM8_BKIN/ADC12_IN6/TIM3_CH1/TIM1_BKIN_42") (pintype "bidirectional"))
    )
    (net (code "120") (name "SPI1_MOSI") (class "Default")
      (node (ref "U2") (pin "43") (pinfunction "PA7/SPI1_MOSI/TIM8_CH1N/ADC12_IN7/TIM3_CH2/TIM1_CH1N_43") (pintype "bidirectional"))
    )
    (net (code "121") (name "SPI1_SCK") (class "Default")
      (node (ref "U2") (pin "41") (pinfunction "PA5/SPI1_SCK/DAC_OUT2/ADC12_IN5_41") (pintype "bidirectional"))
    )
    (net (code "122") (name "USART1_RX") (class "Default")
      (node (ref "U2") (pin "102") (pinfunction "PA10/USART1_RX/TIM1_CH3_102") (pintype "bidirectional"))
    )
    (net (code "123") (name "USART1_TX") (class "Default")
      (node (ref "U2") (pin "101") (pinfunction "PA9/USART1_TX/TIM1_CH2_101") (pintype "bidirectional"))
    )
    (net (code "124") (name "VCC+12V0") (class "Default")
      (node (ref "C1") (pin "2") (pinfunction "2_2") (pintype "passive"))
      (node (ref "U3") (pin "3") (pinfunction "VIN_3") (pintype "passive"))
    )
    (net (code "125") (name "VIN+12V0") (class "Default")
      (node (ref "P2") (pin "1") (pinfunction "1_1") (pintype "passive"))
      (node (ref "P3") (pin "1") (pinfunction "1_1") (pintype "passive"))
      (node (ref "P4") (pin "1") (pinfunction "1_1") (pintype "passive"))
      (node (ref "P5") (pin "1") (pinfunction "1_1") (pintype "passive"))
      (node (ref "P6") (pin "1") (pinfunction "1_1") (pintype "passive"))
    )
    (net (code "126") (name "unconnected-(J1-ID-Pad4)") (class "Default")
      (node (ref "J1") (pin "4") (pinfunction "ID_4") (pintype "passive"))
    )
    (net (code "127") (name "unconnected-(U1-NC-Pad8)") (class "Default")
      (node (ref "U1") (pin "8") (pinfunction "NC_8") (pintype "passive+no_connect"))
    )
    (net (code "128") (name "unconnected-(U1-TONW-Pad15)") (class "Default")
      (node (ref "U1") (pin "15") (pinfunction "TONW_15") (pintype "passive+no_connect"))
    )
    (net (code "129") (name "unconnected-(U1-~{CTS}-Pad9)") (class "Default")
      (node (ref "U1") (pin "9") (pinfunction "~{CTS}_9") (pintype "passive+no_connect"))
    )
    (net (code "130") (name "unconnected-(U1-~{DCD}-Pad12)") (class "Default")
      (node (ref "U1") (pin "12") (pinfunction "~{DCD}_12") (pintype "passive+no_connect"))
    )
    (net (code "131") (name "unconnected-(U1-~{DSR}-Pad10)") (class "Default")
      (node (ref "U1") (pin "10") (pinfunction "~{DSR}_10") (pintype "passive+no_connect"))
    )
    (net (code "132") (name "unconnected-(U1-~{DTR}-Pad13)") (class "Default")
      (node (ref "U1") (pin "13") (pinfunction "~{DTR}_13") (pintype "passive+no_connect"))
    )
    (net (code "133") (name "unconnected-(U1-~{RI}-Pad11)") (class "Default")
      (node (ref "U1") (pin "11") (pinfunction "~{RI}_11") (pintype "passive+no_connect"))
    )
    (net (code "134") (name "unconnected-(U1-~{RST}-Pad7)") (class "Default")
      (node (ref "U1") (pin "7") (pinfunction "~{RST}_7") (pintype "passive+no_connect"))
    )
    (net (code "135") (name "unconnected-(U1-~{RTS}-Pad14)") (class "Default")
      (node (ref "U1") (pin "14") (pinfunction "~{RTS}_14") (pintype "passive+no_connect"))
    )
    (net (code "136") (name "unconnected-(U2-NC-Pad106)") (class "Default")
      (node (ref "U2") (pin "106") (pinfunction "NC_106") (pintype "power_in+no_connect"))
    )
    (net (code "137") (name "unconnected-(U2-PA15{slash}JTDI{slash}SPI3_NSS{slash}I2S3_WS{slash}TIM2_CH1_ETR{slash}SPI1_NSS-Pad110)") (class "Default")
      (node (ref "U2") (pin "110") (pinfunction "PA15/JTDI/SPI3_NSS/I2S3_WS/TIM2_CH1_ETR/SPI1_NSS_110") (pintype "bidirectional+no_connect"))
    )
    (net (code "138") (name "unconnected-(U2-PB1{slash}ADC12_IN9{slash}TIM3_CH4{slash}TIM8_CH3N{slash}TIM1_CH3N-Pad47)") (class "Default")
      (node (ref "U2") (pin "47") (pinfunction "PB1/ADC12_IN9/TIM3_CH4/TIM8_CH3N/TIM1_CH3N_47") (pintype "bidirectional"))
    )
    (net (code "139") (name "unconnected-(U2-PC6{slash}I2S2_MCK{slash}TIM8_CH1{slash}SDIO_D6{slash}TIM3_CH1-Pad96)") (class "Default")
      (node (ref "U2") (pin "96") (pinfunction "PC6/I2S2_MCK/TIM8_CH1/SDIO_D6/TIM3_CH1_96") (pintype "bidirectional"))
    )
    (net (code "140") (name "unconnected-(U2-PC7{slash}I2S3_MCK{slash}TIM8_CH2{slash}SDIO_D7{slash}TIM3_CH2-Pad97)") (class "Default")
      (node (ref "U2") (pin "97") (pinfunction "PC7/I2S3_MCK/TIM8_CH2/SDIO_D7/TIM3_CH2_97") (pintype "bidirectional"))
    )
    (net (code "141") (name "unconnected-(U2-PD6{slash}FSMC_NWAIT{slash}USART2_RX-Pad122)") (class "Default")
      (node (ref "U2") (pin "122") (pinfunction "PD6/FSMC_NWAIT/USART2_RX_122") (pintype "bidirectional"))
    )
    (net (code "142") (name "unconnected-(U2-PD7{slash}FSMC_NE1{slash}FSMC_NCE2{slash}USART2_CK-Pad123)") (class "Default")
      (node (ref "U2") (pin "123") (pinfunction "PD7/FSMC_NE1/FSMC_NCE2/USART2_CK_123") (pintype "bidirectional"))
    )
    (net (code "143") (name "unconnected-(U2-PD10{slash}FSMC_D15{slash}USART3_CK-Pad79)") (class "Default")
      (node (ref "U2") (pin "79") (pinfunction "PD10/FSMC_D15/USART3_CK_79") (pintype "bidirectional"))
    )
    (net (code "144") (name "unconnected-(U2-PD11{slash}FSMC_A16{slash}USART3_CTS-Pad80)") (class "Default")
      (node (ref "U2") (pin "80") (pinfunction "PD11/FSMC_A16/USART3_CTS_80") (pintype "bidirectional"))
    )
    (net (code "145") (name "unconnected-(U2-PD12{slash}FSMC_A17{slash}TIM4_CH1{slash}USART3_RTS-Pad81)") (class "Default")
      (node (ref "U2") (pin "81") (pinfunction "PD12/FSMC_A17/TIM4_CH1/USART3_RTS_81") (pintype "bidirectional"))
    )
    (net (code "146") (name "unconnected-(U2-PD13{slash}FSMC_A18{slash}TIM4_CH2-Pad82)") (class "Default")
      (node (ref "U2") (pin "82") (pinfunction "PD13/FSMC_A18/TIM4_CH2_82") (pintype "bidirectional"))
    )
    (net (code "147") (name "unconnected-(U2-PD14{slash}FSMC_D0{slash}TIM4_CH3-Pad85)") (class "Default")
      (node (ref "U2") (pin "85") (pinfunction "PD14/FSMC_D0/TIM4_CH3_85") (pintype "bidirectional"))
    )
    (net (code "148") (name "unconnected-(U2-PD15{slash}FSMC_D1{slash}TIM4_CH4-Pad86)") (class "Default")
      (node (ref "U2") (pin "86") (pinfunction "PD15/FSMC_D1/TIM4_CH4_86") (pintype "bidirectional"))
    )
    (net (code "149") (name "unconnected-(U2-PF4{slash}FSMC_A4-Pad14)") (class "Default")
      (node (ref "U2") (pin "14") (pinfunction "PF4/FSMC_A4_14") (pintype "bidirectional"))
    )
    (net (code "150") (name "unconnected-(U2-PF5{slash}FSMC_A5-Pad15)") (class "Default")
      (node (ref "U2") (pin "15") (pinfunction "PF5/FSMC_A5_15") (pintype "bidirectional"))
    )
    (net (code "151") (name "unconnected-(U2-PF11{slash}FSMC_NIOS16-Pad49)") (class "Default")
      (node (ref "U2") (pin "49") (pinfunction "PF11/FSMC_NIOS16_49") (pintype "bidirectional"))
    )
    (net (code "152") (name "unconnected-(U2-PF12{slash}FSMC_A6-Pad50)") (class "Default")
      (node (ref "U2") (pin "50") (pinfunction "PF12/FSMC_A6_50") (pintype "bidirectional"))
    )
    (net (code "153") (name "unconnected-(U2-PF13{slash}FSMC_A7-Pad53)") (class "Default")
      (node (ref "U2") (pin "53") (pinfunction "PF13/FSMC_A7_53") (pintype "bidirectional"))
    )
    (net (code "154") (name "unconnected-(U2-PF14{slash}FSMC_A8-Pad54)") (class "Default")
      (node (ref "U2") (pin "54") (pinfunction "PF14/FSMC_A8_54") (pintype "bidirectional"))
    )
    (net (code "155") (name "unconnected-(U2-PF15{slash}FSMC_A9-Pad55)") (class "Default")
      (node (ref "U2") (pin "55") (pinfunction "PF15/FSMC_A9_55") (pintype "bidirectional"))
    )
    (net (code "156") (name "unconnected-(U2-PG8-Pad93)") (class "Default")
      (node (ref "U2") (pin "93") (pinfunction "PG8_93") (pintype "bidirectional"))
    )
    (net (code "157") (name "unconnected-(U2-PG15-Pad132)") (class "Default")
      (node (ref "U2") (pin "132") (pinfunction "PG15_132") (pintype "bidirectional"))
    )
    (net (code "158") (name "unconnected-(U2-VBAT-Pad6)") (class "Default")
      (node (ref "U2") (pin "6") (pinfunction "VBAT_6") (pintype "power_in+no_connect"))
    )
    (net (code "159") (name "unconnected-(U4-NC-Pad4)") (class "Default")
      (node (ref "U4") (pin "4") (pinfunction "NC_4") (pintype "passive+no_connect"))
    )
    (net (code "160") (name "unconnected-(U5-NC-Pad4)") (class "Default")
      (node (ref "U5") (pin "4") (pinfunction "NC_4") (pintype "passive+no_connect"))
    )
  )
)
